# EIB_2xA79026-001_large_pins_v1_2.net
KiCad netlist of a schematic drawn in EAGLE
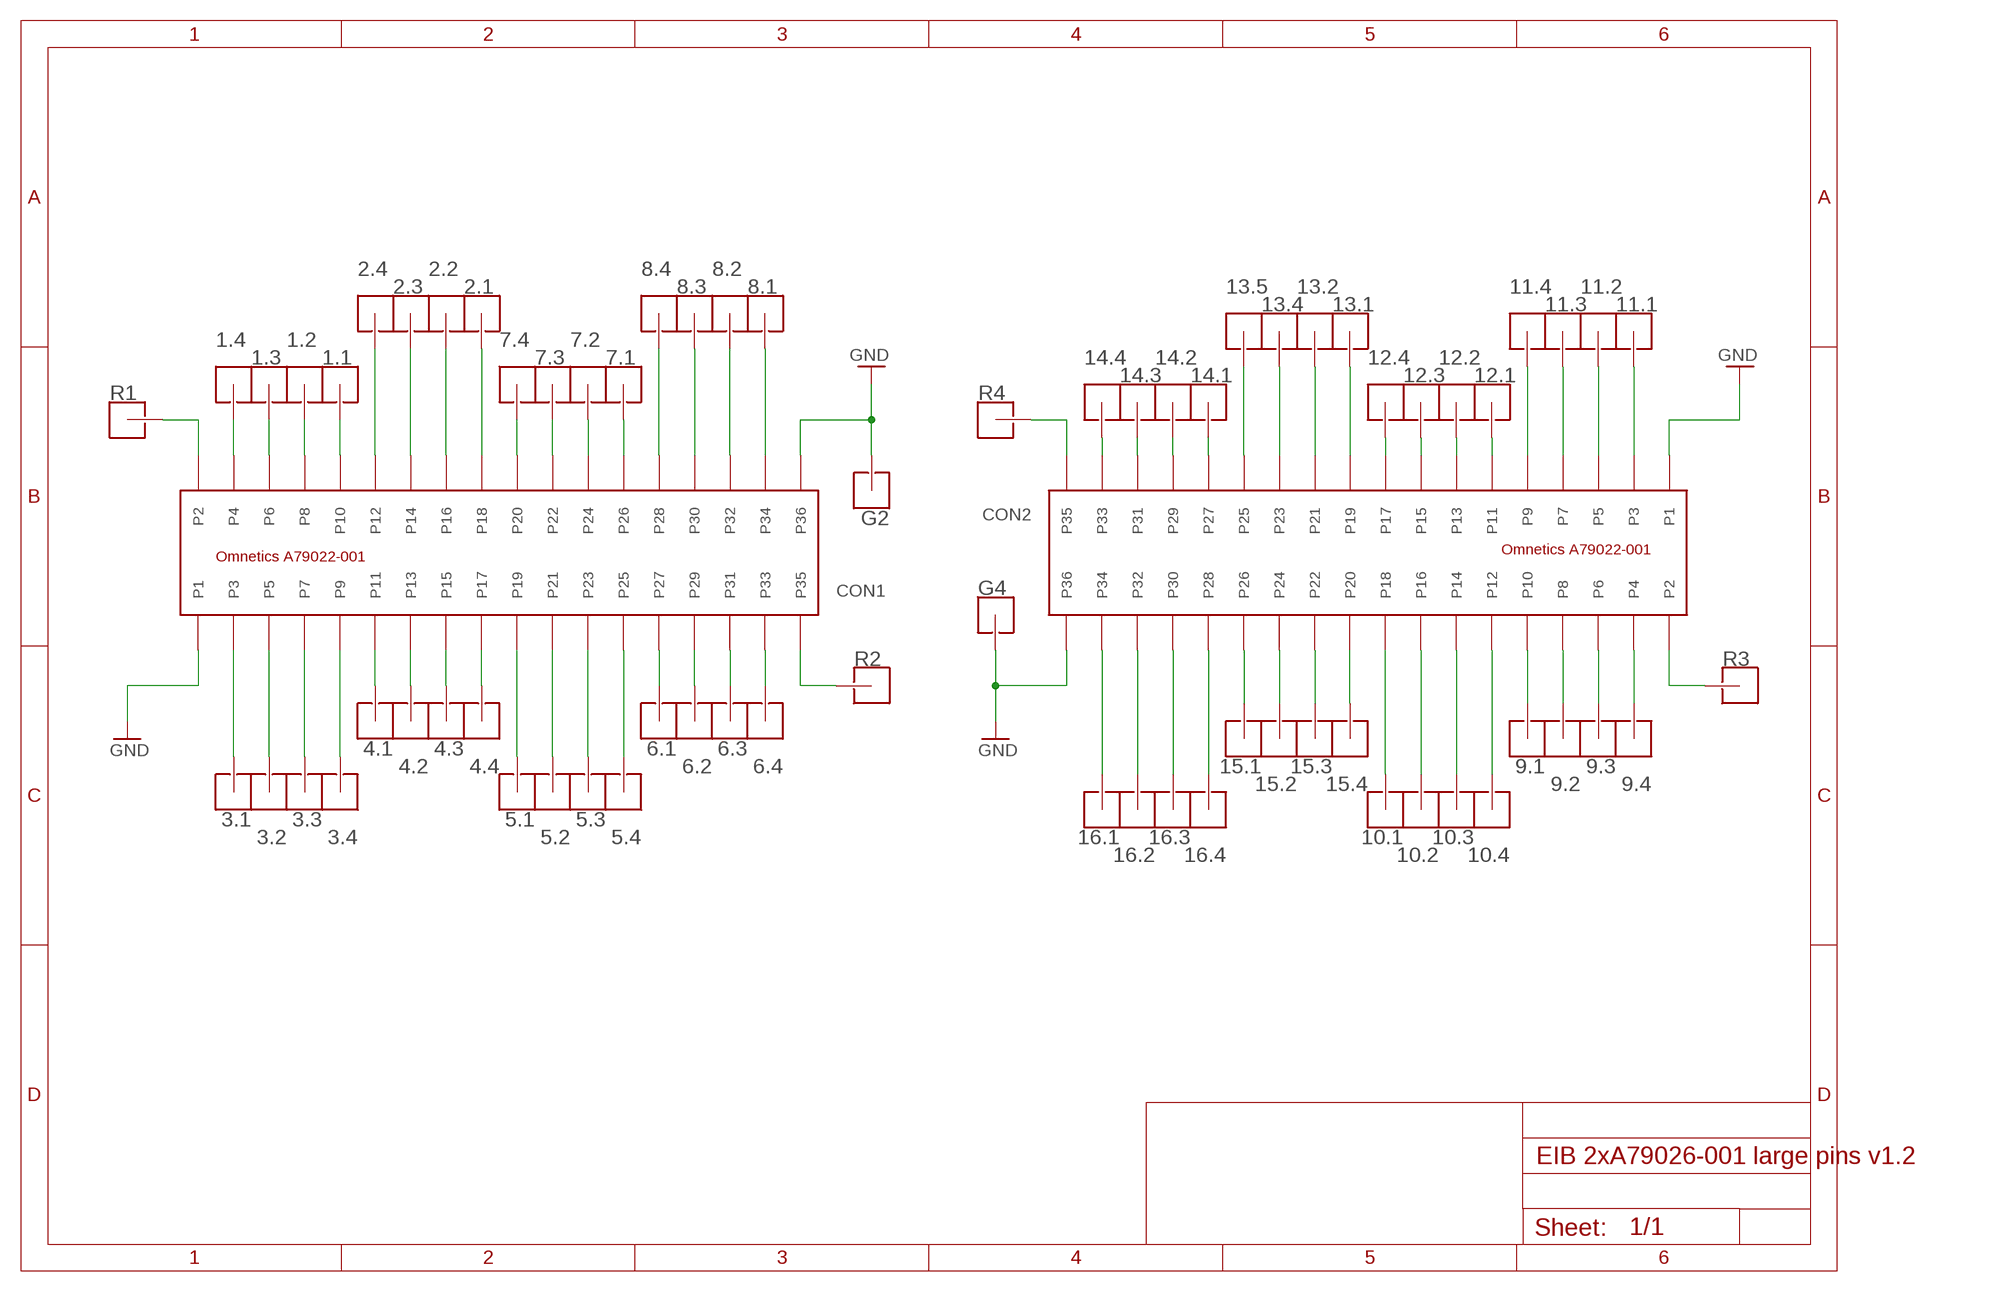
[diagram p0: schematic, sheet 1]

(export (version "E")
  (design (tool "Eeschema 10.0.6"))
  (components
    (comp (ref "1.1")
      (value "HOLE_L_G_PIN_V5")
      (footprint "eagle-import:LARGE_GOLD_PIN_V5")
      (libsource (lib "eagle-import") (part "HOLE_L_G_PIN_V5"))
    )
    (comp (ref "1.2")
      (value "HOLE_L_G_PIN_V5")
      (footprint "eagle-import:LARGE_GOLD_PIN_V5")
      (libsource (lib "eagle-import") (part "HOLE_L_G_PIN_V5"))
    )
    (comp (ref "1.3")
      (value "HOLE_L_G_PIN_V5")
      (footprint "eagle-import:LARGE_GOLD_PIN_V5")
      (libsource (lib "eagle-import") (part "HOLE_L_G_PIN_V5"))
    )
    (comp (ref "1.4")
      (value "HOLE_L_G_PIN_V5")
      (footprint "eagle-import:LARGE_GOLD_PIN_V5")
      (libsource (lib "eagle-import") (part "HOLE_L_G_PIN_V5"))
    )
    (comp (ref "2.1")
      (value "HOLE_L_G_PIN_V5")
      (footprint "eagle-import:LARGE_GOLD_PIN_V5")
      (libsource (lib "eagle-import") (part "HOLE_L_G_PIN_V5"))
    )
    (comp (ref "2.2")
      (value "HOLE_L_G_PIN_V5")
      (footprint "eagle-import:LARGE_GOLD_PIN_V5")
      (libsource (lib "eagle-import") (part "HOLE_L_G_PIN_V5"))
    )
    (comp (ref "2.3")
      (value "HOLE_L_G_PIN_V5")
      (footprint "eagle-import:LARGE_GOLD_PIN_V5")
      (libsource (lib "eagle-import") (part "HOLE_L_G_PIN_V5"))
    )
    (comp (ref "2.4")
      (value "HOLE_L_G_PIN_V5")
      (footprint "eagle-import:LARGE_GOLD_PIN_V5")
      (libsource (lib "eagle-import") (part "HOLE_L_G_PIN_V5"))
    )
    (comp (ref "3.1")
      (value "HOLE_L_G_PIN_V5")
      (footprint "eagle-import:LARGE_GOLD_PIN_V5")
      (libsource (lib "eagle-import") (part "HOLE_L_G_PIN_V5"))
    )
    (comp (ref "3.2")
      (value "HOLE_L_G_PIN_V5")
      (footprint "eagle-import:LARGE_GOLD_PIN_V5")
      (libsource (lib "eagle-import") (part "HOLE_L_G_PIN_V5"))
    )
    (comp (ref "3.3")
      (value "HOLE_L_G_PIN_V5")
      (footprint "eagle-import:LARGE_GOLD_PIN_V5")
      (libsource (lib "eagle-import") (part "HOLE_L_G_PIN_V5"))
    )
    (comp (ref "3.4")
      (value "HOLE_L_G_PIN_V5")
      (footprint "eagle-import:LARGE_GOLD_PIN_V5")
      (libsource (lib "eagle-import") (part "HOLE_L_G_PIN_V5"))
    )
    (comp (ref "4.1")
      (value "HOLE_L_G_PIN_V5")
      (footprint "eagle-import:LARGE_GOLD_PIN_V5")
      (libsource (lib "eagle-import") (part "HOLE_L_G_PIN_V5"))
    )
    (comp (ref "4.2")
      (value "HOLE_L_G_PIN_V5")
      (footprint "eagle-import:LARGE_GOLD_PIN_V5")
      (libsource (lib "eagle-import") (part "HOLE_L_G_PIN_V5"))
    )
    (comp (ref "4.3")
      (value "HOLE_L_G_PIN_V5")
      (footprint "eagle-import:LARGE_GOLD_PIN_V5")
      (libsource (lib "eagle-import") (part "HOLE_L_G_PIN_V5"))
    )
    (comp (ref "4.4")
      (value "HOLE_L_G_PIN_V5")
      (footprint "eagle-import:LARGE_GOLD_PIN_V5")
      (libsource (lib "eagle-import") (part "HOLE_L_G_PIN_V5"))
    )
    (comp (ref "5.1")
      (value "HOLE_L_G_PIN_V5")
      (footprint "eagle-import:LARGE_GOLD_PIN_V5")
      (libsource (lib "eagle-import") (part "HOLE_L_G_PIN_V5"))
    )
    (comp (ref "5.2")
      (value "HOLE_L_G_PIN_V5")
      (footprint "eagle-import:LARGE_GOLD_PIN_V5")
      (libsource (lib "eagle-import") (part "HOLE_L_G_PIN_V5"))
    )
    (comp (ref "5.3")
      (value "HOLE_L_G_PIN_V5")
      (footprint "eagle-import:LARGE_GOLD_PIN_V5")
      (libsource (lib "eagle-import") (part "HOLE_L_G_PIN_V5"))
    )
    (comp (ref "5.4")
      (value "HOLE_L_G_PIN_V5")
      (footprint "eagle-import:LARGE_GOLD_PIN_V5")
      (libsource (lib "eagle-import") (part "HOLE_L_G_PIN_V5"))
    )
    (comp (ref "6.1")
      (value "HOLE_L_G_PIN_V5")
      (footprint "eagle-import:LARGE_GOLD_PIN_V5")
      (libsource (lib "eagle-import") (part "HOLE_L_G_PIN_V5"))
    )
    (comp (ref "6.2")
      (value "HOLE_L_G_PIN_V5")
      (footprint "eagle-import:LARGE_GOLD_PIN_V5")
      (libsource (lib "eagle-import") (part "HOLE_L_G_PIN_V5"))
    )
    (comp (ref "6.3")
      (value "HOLE_L_G_PIN_V5")
      (footprint "eagle-import:LARGE_GOLD_PIN_V5")
      (libsource (lib "eagle-import") (part "HOLE_L_G_PIN_V5"))
    )
    (comp (ref "6.4")
      (value "HOLE_L_G_PIN_V5")
      (footprint "eagle-import:LARGE_GOLD_PIN_V5")
      (libsource (lib "eagle-import") (part "HOLE_L_G_PIN_V5"))
    )
    (comp (ref "7.1")
      (value "HOLE_L_G_PIN_V5")
      (footprint "eagle-import:LARGE_GOLD_PIN_V5")
      (libsource (lib "eagle-import") (part "HOLE_L_G_PIN_V5"))
    )
    (comp (ref "7.2")
      (value "HOLE_L_G_PIN_V5")
      (footprint "eagle-import:LARGE_GOLD_PIN_V5")
      (libsource (lib "eagle-import") (part "HOLE_L_G_PIN_V5"))
    )
    (comp (ref "7.3")
      (value "HOLE_L_G_PIN_V5")
      (footprint "eagle-import:LARGE_GOLD_PIN_V5")
      (libsource (lib "eagle-import") (part "HOLE_L_G_PIN_V5"))
    )
    (comp (ref "7.4")
      (value "HOLE_L_G_PIN_V5")
      (footprint "eagle-import:LARGE_GOLD_PIN_V5")
      (libsource (lib "eagle-import") (part "HOLE_L_G_PIN_V5"))
    )
    (comp (ref "8.1")
      (value "HOLE_L_G_PIN_V5")
      (footprint "eagle-import:LARGE_GOLD_PIN_V5")
      (libsource (lib "eagle-import") (part "HOLE_L_G_PIN_V5"))
    )
    (comp (ref "8.2")
      (value "HOLE_L_G_PIN_V5")
      (footprint "eagle-import:LARGE_GOLD_PIN_V5")
      (libsource (lib "eagle-import") (part "HOLE_L_G_PIN_V5"))
    )
    (comp (ref "8.3")
      (value "HOLE_L_G_PIN_V5")
      (footprint "eagle-import:LARGE_GOLD_PIN_V5")
      (libsource (lib "eagle-import") (part "HOLE_L_G_PIN_V5"))
    )
    (comp (ref "8.4")
      (value "HOLE_L_G_PIN_V5")
      (footprint "eagle-import:LARGE_GOLD_PIN_V5")
      (libsource (lib "eagle-import") (part "HOLE_L_G_PIN_V5"))
    )
    (comp (ref "9.1")
      (value "HOLE_L_G_PIN_V5")
      (footprint "eagle-import:LARGE_GOLD_PIN_V5")
      (libsource (lib "eagle-import") (part "HOLE_L_G_PIN_V5"))
    )
    (comp (ref "9.2")
      (value "HOLE_L_G_PIN_V5")
      (footprint "eagle-import:LARGE_GOLD_PIN_V5")
      (libsource (lib "eagle-import") (part "HOLE_L_G_PIN_V5"))
    )
    (comp (ref "9.3")
      (value "HOLE_L_G_PIN_V5")
      (footprint "eagle-import:LARGE_GOLD_PIN_V5")
      (libsource (lib "eagle-import") (part "HOLE_L_G_PIN_V5"))
    )
    (comp (ref "9.4")
      (value "HOLE_L_G_PIN_V5")
      (footprint "eagle-import:LARGE_GOLD_PIN_V5")
      (libsource (lib "eagle-import") (part "HOLE_L_G_PIN_V5"))
    )
    (comp (ref "10.1")
      (value "HOLE_L_G_PIN_V5")
      (footprint "eagle-import:LARGE_GOLD_PIN_V5")
      (libsource (lib "eagle-import") (part "HOLE_L_G_PIN_V5"))
    )
    (comp (ref "10.2")
      (value "HOLE_L_G_PIN_V5")
      (footprint "eagle-import:LARGE_GOLD_PIN_V5")
      (libsource (lib "eagle-import") (part "HOLE_L_G_PIN_V5"))
    )
    (comp (ref "10.3")
      (value "HOLE_L_G_PIN_V5")
      (footprint "eagle-import:LARGE_GOLD_PIN_V5")
      (libsource (lib "eagle-import") (part "HOLE_L_G_PIN_V5"))
    )
    (comp (ref "10.4")
      (value "HOLE_L_G_PIN_V5")
      (footprint "eagle-import:LARGE_GOLD_PIN_V5")
      (libsource (lib "eagle-import") (part "HOLE_L_G_PIN_V5"))
    )
    (comp (ref "11.1")
      (value "HOLE_L_G_PIN_V5")
      (footprint "eagle-import:LARGE_GOLD_PIN_V5")
      (libsource (lib "eagle-import") (part "HOLE_L_G_PIN_V5"))
    )
    (comp (ref "11.2")
      (value "HOLE_L_G_PIN_V5")
      (footprint "eagle-import:LARGE_GOLD_PIN_V5")
      (libsource (lib "eagle-import") (part "HOLE_L_G_PIN_V5"))
    )
    (comp (ref "11.3")
      (value "HOLE_L_G_PIN_V5")
      (footprint "eagle-import:LARGE_GOLD_PIN_V5")
      (libsource (lib "eagle-import") (part "HOLE_L_G_PIN_V5"))
    )
    (comp (ref "11.4")
      (value "HOLE_L_G_PIN_V5")
      (footprint "eagle-import:LARGE_GOLD_PIN_V5")
      (libsource (lib "eagle-import") (part "HOLE_L_G_PIN_V5"))
    )
    (comp (ref "12.1")
      (value "HOLE_L_G_PIN_V5")
      (footprint "eagle-import:LARGE_GOLD_PIN_V5")
      (libsource (lib "eagle-import") (part "HOLE_L_G_PIN_V5"))
    )
    (comp (ref "12.2")
      (value "HOLE_L_G_PIN_V5")
      (footprint "eagle-import:LARGE_GOLD_PIN_V5")
      (libsource (lib "eagle-import") (part "HOLE_L_G_PIN_V5"))
    )
    (comp (ref "12.3")
      (value "HOLE_L_G_PIN_V5")
      (footprint "eagle-import:LARGE_GOLD_PIN_V5")
      (libsource (lib "eagle-import") (part "HOLE_L_G_PIN_V5"))
    )
    (comp (ref "12.4")
      (value "HOLE_L_G_PIN_V5")
      (footprint "eagle-import:LARGE_GOLD_PIN_V5")
      (libsource (lib "eagle-import") (part "HOLE_L_G_PIN_V5"))
    )
    (comp (ref "13.1")
      (value "HOLE_L_G_PIN_V5")
      (footprint "eagle-import:LARGE_GOLD_PIN_V5")
      (libsource (lib "eagle-import") (part "HOLE_L_G_PIN_V5"))
    )
    (comp (ref "13.2")
      (value "HOLE_L_G_PIN_V5")
      (footprint "eagle-import:LARGE_GOLD_PIN_V5")
      (libsource (lib "eagle-import") (part "HOLE_L_G_PIN_V5"))
    )
    (comp (ref "13.4")
      (value "HOLE_L_G_PIN_V5")
      (footprint "eagle-import:LARGE_GOLD_PIN_V5")
      (libsource (lib "eagle-import") (part "HOLE_L_G_PIN_V5"))
    )
    (comp (ref "13.5")
      (value "HOLE_L_G_PIN_V5")
      (footprint "eagle-import:LARGE_GOLD_PIN_V5")
      (libsource (lib "eagle-import") (part "HOLE_L_G_PIN_V5"))
    )
    (comp (ref "14.1")
      (value "HOLE_L_G_PIN_V5")
      (footprint "eagle-import:LARGE_GOLD_PIN_V5")
      (libsource (lib "eagle-import") (part "HOLE_L_G_PIN_V5"))
    )
    (comp (ref "14.2")
      (value "HOLE_L_G_PIN_V5")
      (footprint "eagle-import:LARGE_GOLD_PIN_V5")
      (libsource (lib "eagle-import") (part "HOLE_L_G_PIN_V5"))
    )
    (comp (ref "14.3")
      (value "HOLE_L_G_PIN_V5")
      (footprint "eagle-import:LARGE_GOLD_PIN_V5")
      (libsource (lib "eagle-import") (part "HOLE_L_G_PIN_V5"))
    )
    (comp (ref "14.4")
      (value "HOLE_L_G_PIN_V5")
      (footprint "eagle-import:LARGE_GOLD_PIN_V5")
      (libsource (lib "eagle-import") (part "HOLE_L_G_PIN_V5"))
    )
    (comp (ref "15.1")
      (value "HOLE_L_G_PIN_V5")
      (footprint "eagle-import:LARGE_GOLD_PIN_V5")
      (libsource (lib "eagle-import") (part "HOLE_L_G_PIN_V5"))
    )
    (comp (ref "15.2")
      (value "HOLE_L_G_PIN_V5")
      (footprint "eagle-import:LARGE_GOLD_PIN_V5")
      (libsource (lib "eagle-import") (part "HOLE_L_G_PIN_V5"))
    )
    (comp (ref "15.3")
      (value "HOLE_L_G_PIN_V5")
      (footprint "eagle-import:LARGE_GOLD_PIN_V5")
      (libsource (lib "eagle-import") (part "HOLE_L_G_PIN_V5"))
    )
    (comp (ref "15.4")
      (value "HOLE_L_G_PIN_V5")
      (footprint "eagle-import:LARGE_GOLD_PIN_V5")
      (libsource (lib "eagle-import") (part "HOLE_L_G_PIN_V5"))
    )
    (comp (ref "16.1")
      (value "HOLE_L_G_PIN_V5")
      (footprint "eagle-import:LARGE_GOLD_PIN_V5")
      (libsource (lib "eagle-import") (part "HOLE_L_G_PIN_V5"))
    )
    (comp (ref "16.2")
      (value "HOLE_L_G_PIN_V5")
      (footprint "eagle-import:LARGE_GOLD_PIN_V5")
      (libsource (lib "eagle-import") (part "HOLE_L_G_PIN_V5"))
    )
    (comp (ref "16.3")
      (value "HOLE_L_G_PIN_V5")
      (footprint "eagle-import:LARGE_GOLD_PIN_V5")
      (libsource (lib "eagle-import") (part "HOLE_L_G_PIN_V5"))
    )
    (comp (ref "16.4")
      (value "HOLE_L_G_PIN_V5")
      (footprint "eagle-import:LARGE_GOLD_PIN_V5")
      (libsource (lib "eagle-import") (part "HOLE_L_G_PIN_V5"))
    )
    (comp (ref "CON1")
      (value "A79022-001_MALESMD")
      (footprint "eagle-import:A79026-001_MALE")
      (libsource (lib "eagle-import") (part "A79022-001_MALESMD"))
    )
    (comp (ref "CON2")
      (value "A79022-001_MALESMD")
      (footprint "eagle-import:A79026-001_MALE")
      (libsource (lib "eagle-import") (part "A79022-001_MALESMD"))
    )
    (comp (ref "G2")
      (value "HOLE_L_G_PIN_V5")
      (footprint "eagle-import:LARGE_GOLD_PIN_V5")
      (libsource (lib "eagle-import") (part "HOLE_L_G_PIN_V5"))
    )
    (comp (ref "G4")
      (value "HOLE_L_G_PIN_V5")
      (footprint "eagle-import:LARGE_GOLD_PIN_V5")
      (libsource (lib "eagle-import") (part "HOLE_L_G_PIN_V5"))
    )
    (comp (ref "R1")
      (value "HOLE_L_G_PIN_V5")
      (footprint "eagle-import:LARGE_GOLD_PIN_V5")
      (libsource (lib "eagle-import") (part "HOLE_L_G_PIN_V5"))
    )
    (comp (ref "R2")
      (value "HOLE_L_G_PIN_V5")
      (footprint "eagle-import:LARGE_GOLD_PIN_V5")
      (libsource (lib "eagle-import") (part "HOLE_L_G_PIN_V5"))
    )
    (comp (ref "R3")
      (value "HOLE_L_G_PIN_V5")
      (footprint "eagle-import:LARGE_GOLD_PIN_V5")
      (libsource (lib "eagle-import") (part "HOLE_L_G_PIN_V5"))
    )
    (comp (ref "R4")
      (value "HOLE_L_G_PIN_V5")
      (footprint "eagle-import:LARGE_GOLD_PIN_V5")
      (libsource (lib "eagle-import") (part "HOLE_L_G_PIN_V5"))
    )
  )
  (nets
    (net (code "1") (name "GND") (class "Default")
      (node (ref "CON1") (pin "P1") (pinfunction "P1_P1") (pintype "bidirectional"))
      (node (ref "CON1") (pin "P36") (pinfunction "P36_P36") (pintype "bidirectional"))
      (node (ref "CON2") (pin "P1") (pinfunction "P1_P1") (pintype "bidirectional"))
      (node (ref "CON2") (pin "P36") (pinfunction "P36_P36") (pintype "bidirectional"))
      (node (ref "G2") (pin "P$1") (pinfunction "P$1_P$1") (pintype "bidirectional"))
      (node (ref "G4") (pin "P$1") (pinfunction "P$1_P$1") (pintype "bidirectional"))
    )
    (net (code "2") (name "Net-(1.1-PadP$1)") (class "Default")
      (node (ref "1.1") (pin "P$1") (pinfunction "P$1_P$1") (pintype "bidirectional"))
      (node (ref "CON1") (pin "P10") (pinfunction "P10_P10") (pintype "bidirectional"))
    )
    (net (code "3") (name "Net-(1.2-PadP$1)") (class "Default")
      (node (ref "1.2") (pin "P$1") (pinfunction "P$1_P$1") (pintype "bidirectional"))
      (node (ref "CON1") (pin "P8") (pinfunction "P8_P8") (pintype "bidirectional"))
    )
    (net (code "4") (name "Net-(1.3-PadP$1)") (class "Default")
      (node (ref "1.3") (pin "P$1") (pinfunction "P$1_P$1") (pintype "bidirectional"))
      (node (ref "CON1") (pin "P6") (pinfunction "P6_P6") (pintype "bidirectional"))
    )
    (net (code "5") (name "Net-(1.4-PadP$1)") (class "Default")
      (node (ref "1.4") (pin "P$1") (pinfunction "P$1_P$1") (pintype "bidirectional"))
      (node (ref "CON1") (pin "P4") (pinfunction "P4_P4") (pintype "bidirectional"))
    )
    (net (code "6") (name "Net-(2.1-PadP$1)") (class "Default")
      (node (ref "2.1") (pin "P$1") (pinfunction "P$1_P$1") (pintype "bidirectional"))
      (node (ref "CON1") (pin "P18") (pinfunction "P18_P18") (pintype "bidirectional"))
    )
    (net (code "7") (name "Net-(2.2-PadP$1)") (class "Default")
      (node (ref "2.2") (pin "P$1") (pinfunction "P$1_P$1") (pintype "bidirectional"))
      (node (ref "CON1") (pin "P16") (pinfunction "P16_P16") (pintype "bidirectional"))
    )
    (net (code "8") (name "Net-(2.3-PadP$1)") (class "Default")
      (node (ref "2.3") (pin "P$1") (pinfunction "P$1_P$1") (pintype "bidirectional"))
      (node (ref "CON1") (pin "P14") (pinfunction "P14_P14") (pintype "bidirectional"))
    )
    (net (code "9") (name "Net-(2.4-PadP$1)") (class "Default")
      (node (ref "2.4") (pin "P$1") (pinfunction "P$1_P$1") (pintype "bidirectional"))
      (node (ref "CON1") (pin "P12") (pinfunction "P12_P12") (pintype "bidirectional"))
    )
    (net (code "10") (name "Net-(3.1-PadP$1)") (class "Default")
      (node (ref "3.1") (pin "P$1") (pinfunction "P$1_P$1") (pintype "bidirectional"))
      (node (ref "CON1") (pin "P3") (pinfunction "P3_P3") (pintype "bidirectional"))
    )
    (net (code "11") (name "Net-(3.2-PadP$1)") (class "Default")
      (node (ref "3.2") (pin "P$1") (pinfunction "P$1_P$1") (pintype "bidirectional"))
      (node (ref "CON1") (pin "P5") (pinfunction "P5_P5") (pintype "bidirectional"))
    )
    (net (code "12") (name "Net-(3.3-PadP$1)") (class "Default")
      (node (ref "3.3") (pin "P$1") (pinfunction "P$1_P$1") (pintype "bidirectional"))
      (node (ref "CON1") (pin "P7") (pinfunction "P7_P7") (pintype "bidirectional"))
    )
    (net (code "13") (name "Net-(3.4-PadP$1)") (class "Default")
      (node (ref "3.4") (pin "P$1") (pinfunction "P$1_P$1") (pintype "bidirectional"))
      (node (ref "CON1") (pin "P9") (pinfunction "P9_P9") (pintype "bidirectional"))
    )
    (net (code "14") (name "Net-(4.1-PadP$1)") (class "Default")
      (node (ref "4.1") (pin "P$1") (pinfunction "P$1_P$1") (pintype "bidirectional"))
      (node (ref "CON1") (pin "P11") (pinfunction "P11_P11") (pintype "bidirectional"))
    )
    (net (code "15") (name "Net-(4.2-PadP$1)") (class "Default")
      (node (ref "4.2") (pin "P$1") (pinfunction "P$1_P$1") (pintype "bidirectional"))
      (node (ref "CON1") (pin "P13") (pinfunction "P13_P13") (pintype "bidirectional"))
    )
    (net (code "16") (name "Net-(4.3-PadP$1)") (class "Default")
      (node (ref "4.3") (pin "P$1") (pinfunction "P$1_P$1") (pintype "bidirectional"))
      (node (ref "CON1") (pin "P15") (pinfunction "P15_P15") (pintype "bidirectional"))
    )
    (net (code "17") (name "Net-(4.4-PadP$1)") (class "Default")
      (node (ref "4.4") (pin "P$1") (pinfunction "P$1_P$1") (pintype "bidirectional"))
      (node (ref "CON1") (pin "P17") (pinfunction "P17_P17") (pintype "bidirectional"))
    )
    (net (code "18") (name "Net-(5.1-PadP$1)") (class "Default")
      (node (ref "5.1") (pin "P$1") (pinfunction "P$1_P$1") (pintype "bidirectional"))
      (node (ref "CON1") (pin "P19") (pinfunction "P19_P19") (pintype "bidirectional"))
    )
    (net (code "19") (name "Net-(5.2-PadP$1)") (class "Default")
      (node (ref "5.2") (pin "P$1") (pinfunction "P$1_P$1") (pintype "bidirectional"))
      (node (ref "CON1") (pin "P21") (pinfunction "P21_P21") (pintype "bidirectional"))
    )
    (net (code "20") (name "Net-(5.3-PadP$1)") (class "Default")
      (node (ref "5.3") (pin "P$1") (pinfunction "P$1_P$1") (pintype "bidirectional"))
      (node (ref "CON1") (pin "P23") (pinfunction "P23_P23") (pintype "bidirectional"))
    )
    (net (code "21") (name "Net-(5.4-PadP$1)") (class "Default")
      (node (ref "5.4") (pin "P$1") (pinfunction "P$1_P$1") (pintype "bidirectional"))
      (node (ref "CON1") (pin "P25") (pinfunction "P25_P25") (pintype "bidirectional"))
    )
    (net (code "22") (name "Net-(6.1-PadP$1)") (class "Default")
      (node (ref "6.1") (pin "P$1") (pinfunction "P$1_P$1") (pintype "bidirectional"))
      (node (ref "CON1") (pin "P27") (pinfunction "P27_P27") (pintype "bidirectional"))
    )
    (net (code "23") (name "Net-(6.2-PadP$1)") (class "Default")
      (node (ref "6.2") (pin "P$1") (pinfunction "P$1_P$1") (pintype "bidirectional"))
      (node (ref "CON1") (pin "P29") (pinfunction "P29_P29") (pintype "bidirectional"))
    )
    (net (code "24") (name "Net-(6.3-PadP$1)") (class "Default")
      (node (ref "6.3") (pin "P$1") (pinfunction "P$1_P$1") (pintype "bidirectional"))
      (node (ref "CON1") (pin "P31") (pinfunction "P31_P31") (pintype "bidirectional"))
    )
    (net (code "25") (name "Net-(6.4-PadP$1)") (class "Default")
      (node (ref "6.4") (pin "P$1") (pinfunction "P$1_P$1") (pintype "bidirectional"))
      (node (ref "CON1") (pin "P33") (pinfunction "P33_P33") (pintype "bidirectional"))
    )
    (net (code "26") (name "Net-(7.1-PadP$1)") (class "Default")
      (node (ref "7.1") (pin "P$1") (pinfunction "P$1_P$1") (pintype "bidirectional"))
      (node (ref "CON1") (pin "P26") (pinfunction "P26_P26") (pintype "bidirectional"))
    )
    (net (code "27") (name "Net-(7.2-PadP$1)") (class "Default")
      (node (ref "7.2") (pin "P$1") (pinfunction "P$1_P$1") (pintype "bidirectional"))
      (node (ref "CON1") (pin "P24") (pinfunction "P24_P24") (pintype "bidirectional"))
    )
    (net (code "28") (name "Net-(7.3-PadP$1)") (class "Default")
      (node (ref "7.3") (pin "P$1") (pinfunction "P$1_P$1") (pintype "bidirectional"))
      (node (ref "CON1") (pin "P22") (pinfunction "P22_P22") (pintype "bidirectional"))
    )
    (net (code "29") (name "Net-(7.4-PadP$1)") (class "Default")
      (node (ref "7.4") (pin "P$1") (pinfunction "P$1_P$1") (pintype "bidirectional"))
      (node (ref "CON1") (pin "P20") (pinfunction "P20_P20") (pintype "bidirectional"))
    )
    (net (code "30") (name "Net-(8.1-PadP$1)") (class "Default")
      (node (ref "8.1") (pin "P$1") (pinfunction "P$1_P$1") (pintype "bidirectional"))
      (node (ref "CON1") (pin "P34") (pinfunction "P34_P34") (pintype "bidirectional"))
    )
    (net (code "31") (name "Net-(8.2-PadP$1)") (class "Default")
      (node (ref "8.2") (pin "P$1") (pinfunction "P$1_P$1") (pintype "bidirectional"))
      (node (ref "CON1") (pin "P32") (pinfunction "P32_P32") (pintype "bidirectional"))
    )
    (net (code "32") (name "Net-(8.3-PadP$1)") (class "Default")
      (node (ref "8.3") (pin "P$1") (pinfunction "P$1_P$1") (pintype "bidirectional"))
      (node (ref "CON1") (pin "P30") (pinfunction "P30_P30") (pintype "bidirectional"))
    )
    (net (code "33") (name "Net-(8.4-PadP$1)") (class "Default")
      (node (ref "8.4") (pin "P$1") (pinfunction "P$1_P$1") (pintype "bidirectional"))
      (node (ref "CON1") (pin "P28") (pinfunction "P28_P28") (pintype "bidirectional"))
    )
    (net (code "34") (name "Net-(9.1-PadP$1)") (class "Default")
      (node (ref "9.1") (pin "P$1") (pinfunction "P$1_P$1") (pintype "bidirectional"))
      (node (ref "CON2") (pin "P10") (pinfunction "P10_P10") (pintype "bidirectional"))
    )
    (net (code "35") (name "Net-(9.2-PadP$1)") (class "Default")
      (node (ref "9.2") (pin "P$1") (pinfunction "P$1_P$1") (pintype "bidirectional"))
      (node (ref "CON2") (pin "P8") (pinfunction "P8_P8") (pintype "bidirectional"))
    )
    (net (code "36") (name "Net-(9.3-PadP$1)") (class "Default")
      (node (ref "9.3") (pin "P$1") (pinfunction "P$1_P$1") (pintype "bidirectional"))
      (node (ref "CON2") (pin "P6") (pinfunction "P6_P6") (pintype "bidirectional"))
    )
    (net (code "37") (name "Net-(9.4-PadP$1)") (class "Default")
      (node (ref "9.4") (pin "P$1") (pinfunction "P$1_P$1") (pintype "bidirectional"))
      (node (ref "CON2") (pin "P4") (pinfunction "P4_P4") (pintype "bidirectional"))
    )
    (net (code "38") (name "Net-(10.1-PadP$1)") (class "Default")
      (node (ref "10.1") (pin "P$1") (pinfunction "P$1_P$1") (pintype "bidirectional"))
      (node (ref "CON2") (pin "P18") (pinfunction "P18_P18") (pintype "bidirectional"))
    )
    (net (code "39") (name "Net-(10.2-PadP$1)") (class "Default")
      (node (ref "10.2") (pin "P$1") (pinfunction "P$1_P$1") (pintype "bidirectional"))
      (node (ref "CON2") (pin "P16") (pinfunction "P16_P16") (pintype "bidirectional"))
    )
    (net (code "40") (name "Net-(10.3-PadP$1)") (class "Default")
      (node (ref "10.3") (pin "P$1") (pinfunction "P$1_P$1") (pintype "bidirectional"))
      (node (ref "CON2") (pin "P14") (pinfunction "P14_P14") (pintype "bidirectional"))
    )
    (net (code "41") (name "Net-(10.4-PadP$1)") (class "Default")
      (node (ref "10.4") (pin "P$1") (pinfunction "P$1_P$1") (pintype "bidirectional"))
      (node (ref "CON2") (pin "P12") (pinfunction "P12_P12") (pintype "bidirectional"))
    )
    (net (code "42") (name "Net-(11.1-PadP$1)") (class "Default")
      (node (ref "11.1") (pin "P$1") (pinfunction "P$1_P$1") (pintype "bidirectional"))
      (node (ref "CON2") (pin "P3") (pinfunction "P3_P3") (pintype "bidirectional"))
    )
    (net (code "43") (name "Net-(11.2-PadP$1)") (class "Default")
      (node (ref "11.2") (pin "P$1") (pinfunction "P$1_P$1") (pintype "bidirectional"))
      (node (ref "CON2") (pin "P5") (pinfunction "P5_P5") (pintype "bidirectional"))
    )
    (net (code "44") (name "Net-(11.3-PadP$1)") (class "Default")
      (node (ref "11.3") (pin "P$1") (pinfunction "P$1_P$1") (pintype "bidirectional"))
      (node (ref "CON2") (pin "P7") (pinfunction "P7_P7") (pintype "bidirectional"))
    )
    (net (code "45") (name "Net-(11.4-PadP$1)") (class "Default")
      (node (ref "11.4") (pin "P$1") (pinfunction "P$1_P$1") (pintype "bidirectional"))
      (node (ref "CON2") (pin "P9") (pinfunction "P9_P9") (pintype "bidirectional"))
    )
    (net (code "46") (name "Net-(12.1-PadP$1)") (class "Default")
      (node (ref "12.1") (pin "P$1") (pinfunction "P$1_P$1") (pintype "bidirectional"))
      (node (ref "CON2") (pin "P11") (pinfunction "P11_P11") (pintype "bidirectional"))
    )
    (net (code "47") (name "Net-(12.2-PadP$1)") (class "Default")
      (node (ref "12.2") (pin "P$1") (pinfunction "P$1_P$1") (pintype "bidirectional"))
      (node (ref "CON2") (pin "P13") (pinfunction "P13_P13") (pintype "bidirectional"))
    )
    (net (code "48") (name "Net-(12.3-PadP$1)") (class "Default")
      (node (ref "12.3") (pin "P$1") (pinfunction "P$1_P$1") (pintype "bidirectional"))
      (node (ref "CON2") (pin "P15") (pinfunction "P15_P15") (pintype "bidirectional"))
    )
    (net (code "49") (name "Net-(12.4-PadP$1)") (class "Default")
      (node (ref "12.4") (pin "P$1") (pinfunction "P$1_P$1") (pintype "bidirectional"))
      (node (ref "CON2") (pin "P17") (pinfunction "P17_P17") (pintype "bidirectional"))
    )
    (net (code "50") (name "Net-(13.1-PadP$1)") (class "Default")
      (node (ref "13.1") (pin "P$1") (pinfunction "P$1_P$1") (pintype "bidirectional"))
      (node (ref "CON2") (pin "P19") (pinfunction "P19_P19") (pintype "bidirectional"))
    )
    (net (code "51") (name "Net-(13.2-PadP$1)") (class "Default")
      (node (ref "13.2") (pin "P$1") (pinfunction "P$1_P$1") (pintype "bidirectional"))
      (node (ref "CON2") (pin "P21") (pinfunction "P21_P21") (pintype "bidirectional"))
    )
    (net (code "52") (name "Net-(13.4-PadP$1)") (class "Default")
      (node (ref "13.4") (pin "P$1") (pinfunction "P$1_P$1") (pintype "bidirectional"))
      (node (ref "CON2") (pin "P23") (pinfunction "P23_P23") (pintype "bidirectional"))
    )
    (net (code "53") (name "Net-(13.5-PadP$1)") (class "Default")
      (node (ref "13.5") (pin "P$1") (pinfunction "P$1_P$1") (pintype "bidirectional"))
      (node (ref "CON2") (pin "P25") (pinfunction "P25_P25") (pintype "bidirectional"))
    )
    (net (code "54") (name "Net-(14.1-PadP$1)") (class "Default")
      (node (ref "14.1") (pin "P$1") (pinfunction "P$1_P$1") (pintype "bidirectional"))
      (node (ref "CON2") (pin "P27") (pinfunction "P27_P27") (pintype "bidirectional"))
    )
    (net (code "55") (name "Net-(14.2-PadP$1)") (class "Default")
      (node (ref "14.2") (pin "P$1") (pinfunction "P$1_P$1") (pintype "bidirectional"))
      (node (ref "CON2") (pin "P29") (pinfunction "P29_P29") (pintype "bidirectional"))
    )
    (net (code "56") (name "Net-(14.3-PadP$1)") (class "Default")
      (node (ref "14.3") (pin "P$1") (pinfunction "P$1_P$1") (pintype "bidirectional"))
      (node (ref "CON2") (pin "P31") (pinfunction "P31_P31") (pintype "bidirectional"))
    )
    (net (code "57") (name "Net-(14.4-PadP$1)") (class "Default")
      (node (ref "14.4") (pin "P$1") (pinfunction "P$1_P$1") (pintype "bidirectional"))
      (node (ref "CON2") (pin "P33") (pinfunction "P33_P33") (pintype "bidirectional"))
    )
    (net (code "58") (name "Net-(15.1-PadP$1)") (class "Default")
      (node (ref "15.1") (pin "P$1") (pinfunction "P$1_P$1") (pintype "bidirectional"))
      (node (ref "CON2") (pin "P26") (pinfunction "P26_P26") (pintype "bidirectional"))
    )
    (net (code "59") (name "Net-(15.2-PadP$1)") (class "Default")
      (node (ref "15.2") (pin "P$1") (pinfunction "P$1_P$1") (pintype "bidirectional"))
      (node (ref "CON2") (pin "P24") (pinfunction "P24_P24") (pintype "bidirectional"))
    )
    (net (code "60") (name "Net-(15.3-PadP$1)") (class "Default")
      (node (ref "15.3") (pin "P$1") (pinfunction "P$1_P$1") (pintype "bidirectional"))
      (node (ref "CON2") (pin "P22") (pinfunction "P22_P22") (pintype "bidirectional"))
    )
    (net (code "61") (name "Net-(15.4-PadP$1)") (class "Default")
      (node (ref "15.4") (pin "P$1") (pinfunction "P$1_P$1") (pintype "bidirectional"))
      (node (ref "CON2") (pin "P20") (pinfunction "P20_P20") (pintype "bidirectional"))
    )
    (net (code "62") (name "Net-(16.1-PadP$1)") (class "Default")
      (node (ref "16.1") (pin "P$1") (pinfunction "P$1_P$1") (pintype "bidirectional"))
      (node (ref "CON2") (pin "P34") (pinfunction "P34_P34") (pintype "bidirectional"))
    )
    (net (code "63") (name "Net-(16.2-PadP$1)") (class "Default")
      (node (ref "16.2") (pin "P$1") (pinfunction "P$1_P$1") (pintype "bidirectional"))
      (node (ref "CON2") (pin "P32") (pinfunction "P32_P32") (pintype "bidirectional"))
    )
    (net (code "64") (name "Net-(16.3-PadP$1)") (class "Default")
      (node (ref "16.3") (pin "P$1") (pinfunction "P$1_P$1") (pintype "bidirectional"))
      (node (ref "CON2") (pin "P30") (pinfunction "P30_P30") (pintype "bidirectional"))
    )
    (net (code "65") (name "Net-(16.4-PadP$1)") (class "Default")
      (node (ref "16.4") (pin "P$1") (pinfunction "P$1_P$1") (pintype "bidirectional"))
      (node (ref "CON2") (pin "P28") (pinfunction "P28_P28") (pintype "bidirectional"))
    )
    (net (code "66") (name "Net-(CON1-PadP2)") (class "Default")
      (node (ref "CON1") (pin "P2") (pinfunction "P2_P2") (pintype "bidirectional"))
      (node (ref "R1") (pin "P$1") (pinfunction "P$1_P$1") (pintype "bidirectional"))
    )
    (net (code "67") (name "Net-(CON1-PadP35)") (class "Default")
      (node (ref "CON1") (pin "P35") (pinfunction "P35_P35") (pintype "bidirectional"))
      (node (ref "R2") (pin "P$1") (pinfunction "P$1_P$1") (pintype "bidirectional"))
    )
    (net (code "68") (name "Net-(CON2-PadP2)") (class "Default")
      (node (ref "CON2") (pin "P2") (pinfunction "P2_P2") (pintype "bidirectional"))
      (node (ref "R3") (pin "P$1") (pinfunction "P$1_P$1") (pintype "bidirectional"))
    )
    (net (code "69") (name "Net-(CON2-PadP35)") (class "Default")
      (node (ref "CON2") (pin "P35") (pinfunction "P35_P35") (pintype "bidirectional"))
      (node (ref "R4") (pin "P$1") (pinfunction "P$1_P$1") (pintype "bidirectional"))
    )
  )
)
